# 64_Electrode_Inverted_Microscope_Schemat.net
KiCad netlist of a schematic drawn in Altium Designer
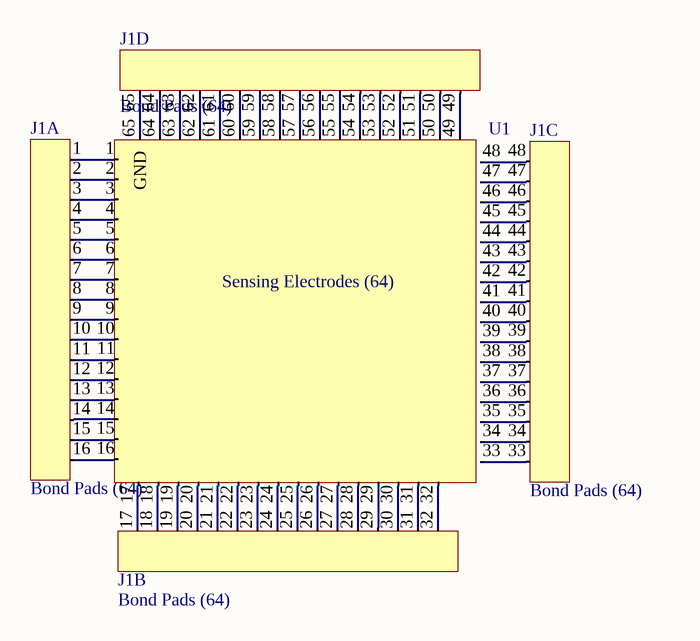
[diagram p0: 64 Electrode Inverted Microscope Schematic.SchDoc]

(export (version "E")
  (design (tool "Eeschema 10.0.6"))
  (components
    (comp (ref "J1")
      (value "Bond Pads (64)")
      (footprint "64 Electrode Footprint (Inverted Microscope)")
      (description "64 Bond pads for 64 channel inverted microscope wa")
      (fields (field (name "PART NUMBER") "Bond Pads (64—Inverted Microscope)"))
      (libsource (lib "Celestial Library Database") (part "Bond Pads (64)"))
    )
    (comp (ref "U1")
      (value "Sensing Electrodes (64)")
      (footprint "64 Electrode Sensing Area (Inverted Microscope)")
      (description "64 electrodes covering a 2 mm by 2mm area")
      (fields (field (name "PART NUMBER") "64 Electrode Sensing Area (Inverted Microscope)"))
      (libsource (lib "Celestial Library Database") (part "Sensing Electrodes (64)"))
    )
  )
  (nets
    (net (code "1") (name "Net-(J1-Pad1)") (class "Default")
      (node (ref "J1") (pin "1") (pintype "output"))
      (node (ref "U1") (pin "1") (pintype "input"))
    )
    (net (code "2") (name "Net-(J1-Pad2)") (class "Default")
      (node (ref "J1") (pin "2") (pintype "output"))
      (node (ref "U1") (pin "2") (pintype "input"))
    )
    (net (code "3") (name "Net-(J1-Pad3)") (class "Default")
      (node (ref "J1") (pin "3") (pintype "output"))
      (node (ref "U1") (pin "3") (pintype "input"))
    )
    (net (code "4") (name "Net-(J1-Pad4)") (class "Default")
      (node (ref "J1") (pin "4") (pintype "output"))
      (node (ref "U1") (pin "4") (pintype "input"))
    )
    (net (code "5") (name "Net-(J1-Pad5)") (class "Default")
      (node (ref "J1") (pin "5") (pintype "output"))
      (node (ref "U1") (pin "5") (pintype "input"))
    )
    (net (code "6") (name "Net-(J1-Pad6)") (class "Default")
      (node (ref "J1") (pin "6") (pintype "output"))
      (node (ref "U1") (pin "6") (pintype "input"))
    )
    (net (code "7") (name "Net-(J1-Pad7)") (class "Default")
      (node (ref "J1") (pin "7") (pintype "output"))
      (node (ref "U1") (pin "7") (pintype "input"))
    )
    (net (code "8") (name "Net-(J1-Pad8)") (class "Default")
      (node (ref "J1") (pin "8") (pintype "output"))
      (node (ref "U1") (pin "8") (pintype "input"))
    )
    (net (code "9") (name "Net-(J1-Pad9)") (class "Default")
      (node (ref "J1") (pin "9") (pintype "output"))
      (node (ref "U1") (pin "9") (pintype "input"))
    )
    (net (code "10") (name "Net-(J1-Pad10)") (class "Default")
      (node (ref "J1") (pin "10") (pintype "output"))
      (node (ref "U1") (pin "10") (pintype "input"))
    )
    (net (code "11") (name "Net-(J1-Pad11)") (class "Default")
      (node (ref "J1") (pin "11") (pintype "output"))
      (node (ref "U1") (pin "11") (pintype "input"))
    )
    (net (code "12") (name "Net-(J1-Pad12)") (class "Default")
      (node (ref "J1") (pin "12") (pintype "output"))
      (node (ref "U1") (pin "12") (pintype "input"))
    )
    (net (code "13") (name "Net-(J1-Pad13)") (class "Default")
      (node (ref "J1") (pin "13") (pintype "output"))
      (node (ref "U1") (pin "13") (pintype "input"))
    )
    (net (code "14") (name "Net-(J1-Pad14)") (class "Default")
      (node (ref "J1") (pin "14") (pintype "output"))
      (node (ref "U1") (pin "14") (pintype "input"))
    )
    (net (code "15") (name "Net-(J1-Pad15)") (class "Default")
      (node (ref "J1") (pin "15") (pintype "output"))
      (node (ref "U1") (pin "15") (pintype "input"))
    )
    (net (code "16") (name "Net-(J1-Pad16)") (class "Default")
      (node (ref "J1") (pin "16") (pintype "output"))
      (node (ref "U1") (pin "16") (pintype "input"))
    )
    (net (code "17") (name "Net-(J1-Pad17)") (class "Default")
      (node (ref "J1") (pin "17") (pintype "output"))
      (node (ref "U1") (pin "17") (pintype "input"))
    )
    (net (code "18") (name "Net-(J1-Pad18)") (class "Default")
      (node (ref "J1") (pin "18") (pintype "output"))
      (node (ref "U1") (pin "18") (pintype "input"))
    )
    (net (code "19") (name "Net-(J1-Pad19)") (class "Default")
      (node (ref "J1") (pin "19") (pintype "output"))
      (node (ref "U1") (pin "19") (pintype "input"))
    )
    (net (code "20") (name "Net-(J1-Pad20)") (class "Default")
      (node (ref "J1") (pin "20") (pintype "output"))
      (node (ref "U1") (pin "20") (pintype "input"))
    )
    (net (code "21") (name "Net-(J1-Pad21)") (class "Default")
      (node (ref "J1") (pin "21") (pintype "output"))
      (node (ref "U1") (pin "21") (pintype "input"))
    )
    (net (code "22") (name "Net-(J1-Pad22)") (class "Default")
      (node (ref "J1") (pin "22") (pintype "output"))
      (node (ref "U1") (pin "22") (pintype "input"))
    )
    (net (code "23") (name "Net-(J1-Pad23)") (class "Default")
      (node (ref "J1") (pin "23") (pintype "output"))
      (node (ref "U1") (pin "23") (pintype "input"))
    )
    (net (code "24") (name "Net-(J1-Pad24)") (class "Default")
      (node (ref "J1") (pin "24") (pintype "output"))
      (node (ref "U1") (pin "24") (pintype "input"))
    )
    (net (code "25") (name "Net-(J1-Pad25)") (class "Default")
      (node (ref "J1") (pin "25") (pintype "output"))
      (node (ref "U1") (pin "25") (pintype "input"))
    )
    (net (code "26") (name "Net-(J1-Pad26)") (class "Default")
      (node (ref "J1") (pin "26") (pintype "output"))
      (node (ref "U1") (pin "26") (pintype "input"))
    )
    (net (code "27") (name "Net-(J1-Pad27)") (class "Default")
      (node (ref "J1") (pin "27") (pintype "output"))
      (node (ref "U1") (pin "27") (pintype "input"))
    )
    (net (code "28") (name "Net-(J1-Pad28)") (class "Default")
      (node (ref "J1") (pin "28") (pintype "output"))
      (node (ref "U1") (pin "28") (pintype "input"))
    )
    (net (code "29") (name "Net-(J1-Pad29)") (class "Default")
      (node (ref "J1") (pin "29") (pintype "output"))
      (node (ref "U1") (pin "29") (pintype "input"))
    )
    (net (code "30") (name "Net-(J1-Pad30)") (class "Default")
      (node (ref "J1") (pin "30") (pintype "output"))
      (node (ref "U1") (pin "30") (pintype "input"))
    )
    (net (code "31") (name "Net-(J1-Pad31)") (class "Default")
      (node (ref "J1") (pin "31") (pintype "output"))
      (node (ref "U1") (pin "31") (pintype "input"))
    )
    (net (code "32") (name "Net-(J1-Pad32)") (class "Default")
      (node (ref "J1") (pin "32") (pintype "output"))
      (node (ref "U1") (pin "32") (pintype "input"))
    )
    (net (code "33") (name "Net-(J1-Pad33)") (class "Default")
      (node (ref "J1") (pin "33") (pintype "output"))
      (node (ref "U1") (pin "33") (pintype "input"))
    )
    (net (code "34") (name "Net-(J1-Pad34)") (class "Default")
      (node (ref "J1") (pin "34") (pintype "output"))
      (node (ref "U1") (pin "34") (pintype "input"))
    )
    (net (code "35") (name "Net-(J1-Pad35)") (class "Default")
      (node (ref "J1") (pin "35") (pintype "output"))
      (node (ref "U1") (pin "35") (pintype "input"))
    )
    (net (code "36") (name "Net-(J1-Pad36)") (class "Default")
      (node (ref "J1") (pin "36") (pintype "output"))
      (node (ref "U1") (pin "36") (pintype "input"))
    )
    (net (code "37") (name "Net-(J1-Pad37)") (class "Default")
      (node (ref "J1") (pin "37") (pintype "output"))
      (node (ref "U1") (pin "37") (pintype "input"))
    )
    (net (code "38") (name "Net-(J1-Pad38)") (class "Default")
      (node (ref "J1") (pin "38") (pintype "output"))
      (node (ref "U1") (pin "38") (pintype "input"))
    )
    (net (code "39") (name "Net-(J1-Pad39)") (class "Default")
      (node (ref "J1") (pin "39") (pintype "output"))
      (node (ref "U1") (pin "39") (pintype "input"))
    )
    (net (code "40") (name "Net-(J1-Pad40)") (class "Default")
      (node (ref "J1") (pin "40") (pintype "output"))
      (node (ref "U1") (pin "40") (pintype "input"))
    )
    (net (code "41") (name "Net-(J1-Pad41)") (class "Default")
      (node (ref "J1") (pin "41") (pintype "output"))
      (node (ref "U1") (pin "41") (pintype "input"))
    )
    (net (code "42") (name "Net-(J1-Pad42)") (class "Default")
      (node (ref "J1") (pin "42") (pintype "output"))
      (node (ref "U1") (pin "42") (pintype "input"))
    )
    (net (code "43") (name "Net-(J1-Pad43)") (class "Default")
      (node (ref "J1") (pin "43") (pintype "output"))
      (node (ref "U1") (pin "43") (pintype "input"))
    )
    (net (code "44") (name "Net-(J1-Pad44)") (class "Default")
      (node (ref "J1") (pin "44") (pintype "output"))
      (node (ref "U1") (pin "44") (pintype "input"))
    )
    (net (code "45") (name "Net-(J1-Pad45)") (class "Default")
      (node (ref "J1") (pin "45") (pintype "output"))
      (node (ref "U1") (pin "45") (pintype "input"))
    )
    (net (code "46") (name "Net-(J1-Pad46)") (class "Default")
      (node (ref "J1") (pin "46") (pintype "output"))
      (node (ref "U1") (pin "46") (pintype "input"))
    )
    (net (code "47") (name "Net-(J1-Pad47)") (class "Default")
      (node (ref "J1") (pin "47") (pintype "output"))
      (node (ref "U1") (pin "47") (pintype "input"))
    )
    (net (code "48") (name "Net-(J1-Pad48)") (class "Default")
      (node (ref "J1") (pin "48") (pintype "output"))
      (node (ref "U1") (pin "48") (pintype "input"))
    )
    (net (code "49") (name "Net-(J1-Pad49)") (class "Default")
      (node (ref "J1") (pin "49") (pintype "output"))
      (node (ref "U1") (pin "49") (pintype "input"))
    )
    (net (code "50") (name "Net-(J1-Pad50)") (class "Default")
      (node (ref "J1") (pin "50") (pintype "output"))
      (node (ref "U1") (pin "50") (pintype "input"))
    )
    (net (code "51") (name "Net-(J1-Pad51)") (class "Default")
      (node (ref "J1") (pin "51") (pintype "output"))
      (node (ref "U1") (pin "51") (pintype "input"))
    )
    (net (code "52") (name "Net-(J1-Pad52)") (class "Default")
      (node (ref "J1") (pin "52") (pintype "output"))
      (node (ref "U1") (pin "52") (pintype "input"))
    )
    (net (code "53") (name "Net-(J1-Pad53)") (class "Default")
      (node (ref "J1") (pin "53") (pintype "output"))
      (node (ref "U1") (pin "53") (pintype "input"))
    )
    (net (code "54") (name "Net-(J1-Pad54)") (class "Default")
      (node (ref "J1") (pin "54") (pintype "output"))
      (node (ref "U1") (pin "54") (pintype "input"))
    )
    (net (code "55") (name "Net-(J1-Pad55)") (class "Default")
      (node (ref "J1") (pin "55") (pintype "output"))
      (node (ref "U1") (pin "55") (pintype "input"))
    )
    (net (code "56") (name "Net-(J1-Pad56)") (class "Default")
      (node (ref "J1") (pin "56") (pintype "output"))
      (node (ref "U1") (pin "56") (pintype "input"))
    )
    (net (code "57") (name "Net-(J1-Pad57)") (class "Default")
      (node (ref "J1") (pin "57") (pintype "output"))
      (node (ref "U1") (pin "57") (pintype "input"))
    )
    (net (code "58") (name "Net-(J1-Pad58)") (class "Default")
      (node (ref "J1") (pin "58") (pintype "output"))
      (node (ref "U1") (pin "58") (pintype "input"))
    )
    (net (code "59") (name "Net-(J1-Pad59)") (class "Default")
      (node (ref "J1") (pin "59") (pintype "output"))
      (node (ref "U1") (pin "59") (pintype "input"))
    )
    (net (code "60") (name "Net-(J1-Pad60)") (class "Default")
      (node (ref "J1") (pin "60") (pintype "output"))
      (node (ref "U1") (pin "60") (pintype "input"))
    )
    (net (code "61") (name "Net-(J1-Pad61)") (class "Default")
      (node (ref "J1") (pin "61") (pintype "output"))
      (node (ref "U1") (pin "61") (pintype "input"))
    )
    (net (code "62") (name "Net-(J1-Pad62)") (class "Default")
      (node (ref "J1") (pin "62") (pintype "output"))
      (node (ref "U1") (pin "62") (pintype "input"))
    )
    (net (code "63") (name "Net-(J1-Pad63)") (class "Default")
      (node (ref "J1") (pin "63") (pintype "output"))
      (node (ref "U1") (pin "63") (pintype "input"))
    )
    (net (code "64") (name "Net-(J1-Pad64)") (class "Default")
      (node (ref "J1") (pin "64") (pintype "output"))
      (node (ref "U1") (pin "64") (pintype "input"))
    )
    (net (code "65") (name "Net-(U1-GND)") (class "Default")
      (node (ref "J1") (pin "65") (pintype "power_in"))
      (node (ref "U1") (pin "65") (pinfunction "GND_65") (pintype "power_in"))
    )
  )
)
